# networking-bridge.net
KiCad netlist of a schematic drawn in EAGLE
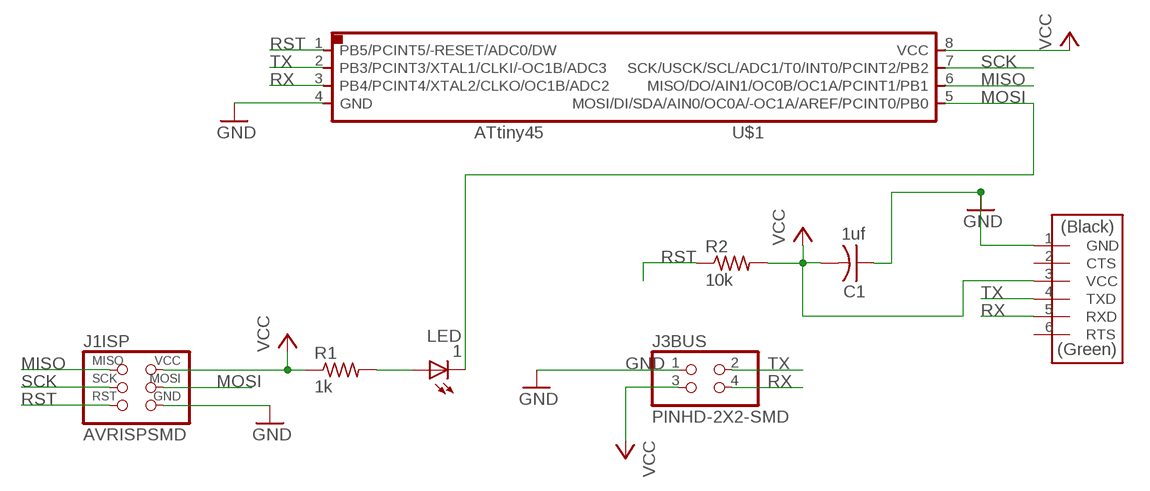
[diagram p0: schematic, sheet 1]

(export (version "E")
  (design (tool "Eeschema 10.0.6"))
  (components
    (comp (ref "1")
      (value "LED")
      (footprint "eagle-import:LED1206")
      (libsource (lib "eagle-import") (part "LED"))
    )
    (comp (ref "C1")
      (value "1uf")
      (footprint "eagle-import:C1206FAB")
      (libsource (lib "eagle-import") (part "CAP-US1206FAB"))
    )
    (comp (ref "J1ISP")
      (value "AVRISPSMD")
      (footprint "eagle-import:2X03SMD")
      (libsource (lib "eagle-import") (part "AVRISPSMD"))
    )
    (comp (ref "J3BUS")
      (value "PINHD-2X2-SMD")
      (footprint "eagle-import:2X02SMD")
      (libsource (lib "eagle-import") (part "PINHD-2X2-SMD"))
    )
    (comp (ref "R1")
      (value "1k")
      (footprint "eagle-import:R1206")
      (libsource (lib "eagle-import") (part "RES-US1206"))
    )
    (comp (ref "R2")
      (value "10k")
      (footprint "eagle-import:R1206")
      (libsource (lib "eagle-import") (part "RES-US1206"))
    )
    (comp (ref "U$1")
      (value "ATTINY45SI")
      (footprint "eagle-import:SOIC8")
      (libsource (lib "eagle-import") (part "ATTINY45SI"))
    )
    (comp (ref "U$2")
      (value "FTDI-SMD-HEADER")
      (footprint "eagle-import:1X06SMD")
      (libsource (lib "eagle-import") (part "FTDI-SMD-HEADER"))
    )
  )
  (nets
    (net (code "1") (name "/MISO") (class "Default")
      (node (ref "J1ISP") (pin "1") (pinfunction "MISO_1") (pintype "passive"))
      (node (ref "U$1") (pin "6") (pinfunction "MISO/DO/AIN1/OC0B/OC1A/PCINT1/PB1_6") (pintype "bidirectional"))
    )
    (net (code "2") (name "/MOSI") (class "Default")
      (node (ref "1") (pin "2") (pinfunction "C_2") (pintype "passive"))
      (node (ref "J1ISP") (pin "4") (pinfunction "MOSI_4") (pintype "passive"))
      (node (ref "U$1") (pin "5") (pinfunction "MOSI/DI/SDA/AIN0/OC0A/-OC1A/AREF/PCINT0/PB0_5") (pintype "bidirectional"))
    )
    (net (code "3") (name "/RST") (class "Default")
      (node (ref "J1ISP") (pin "5") (pinfunction "RST_5") (pintype "passive"))
      (node (ref "R2") (pin "1") (pinfunction "1_1") (pintype "passive"))
      (node (ref "U$1") (pin "1") (pinfunction "PB5/PCINT5/-RESET/ADC0/DW_1") (pintype "bidirectional"))
    )
    (net (code "4") (name "/RX") (class "Default")
      (node (ref "J3BUS") (pin "4") (pinfunction "4_4") (pintype "passive"))
      (node (ref "U$1") (pin "3") (pinfunction "PB4/PCINT4/XTAL2/CLKO/OC1B/ADC2_3") (pintype "bidirectional"))
      (node (ref "U$2") (pin "5") (pinfunction "RXD_5") (pintype "bidirectional"))
    )
    (net (code "5") (name "/SCK") (class "Default")
      (node (ref "J1ISP") (pin "3") (pinfunction "SCK_3") (pintype "passive"))
      (node (ref "U$1") (pin "7") (pinfunction "SCK/USCK/SCL/ADC1/T0/INT0/PCINT2/PB2_7") (pintype "bidirectional"))
    )
    (net (code "6") (name "/TX") (class "Default")
      (node (ref "J3BUS") (pin "2") (pinfunction "2_2") (pintype "passive"))
      (node (ref "U$1") (pin "2") (pinfunction "PB3/PCINT3/XTAL1/CLKI/-OC1B/ADC3_2") (pintype "bidirectional"))
      (node (ref "U$2") (pin "4") (pinfunction "TXD_4") (pintype "bidirectional"))
    )
    (net (code "7") (name "GND") (class "Default")
      (node (ref "C1") (pin "1") (pinfunction "1_1") (pintype "passive"))
      (node (ref "J1ISP") (pin "6") (pinfunction "GND_6") (pintype "passive"))
      (node (ref "J3BUS") (pin "1") (pinfunction "1_1") (pintype "passive"))
      (node (ref "U$1") (pin "4") (pinfunction "GND_4") (pintype "bidirectional"))
      (node (ref "U$2") (pin "1") (pinfunction "GND_1") (pintype "bidirectional"))
    )
    (net (code "8") (name "Net-(1-A)") (class "Default")
      (node (ref "1") (pin "1") (pinfunction "A_1") (pintype "passive"))
      (node (ref "R1") (pin "2") (pinfunction "2_2") (pintype "passive"))
    )
    (net (code "9") (name "VCC") (class "Default")
      (node (ref "C1") (pin "2") (pinfunction "2_2") (pintype "passive"))
      (node (ref "J1ISP") (pin "2") (pinfunction "VCC_2") (pintype "passive"))
      (node (ref "J3BUS") (pin "3") (pinfunction "3_3") (pintype "passive"))
      (node (ref "R1") (pin "1") (pinfunction "1_1") (pintype "passive"))
      (node (ref "R2") (pin "2") (pinfunction "2_2") (pintype "passive"))
      (node (ref "U$1") (pin "8") (pinfunction "VCC_8") (pintype "bidirectional"))
      (node (ref "U$2") (pin "3") (pinfunction "VCC_3") (pintype "bidirectional"))
    )
    (net (code "10") (name "unconnected-(U$2-CTS-Pad2)") (class "Default")
      (node (ref "U$2") (pin "2") (pinfunction "CTS_2") (pintype "bidirectional"))
    )
    (net (code "11") (name "unconnected-(U$2-RTS-Pad6)") (class "Default")
      (node (ref "U$2") (pin "6") (pinfunction "RTS_6") (pintype "bidirectional"))
    )
  )
)
